# xxxxxx_001_sh2_RTC.net
KiCad netlist of a schematic drawn in Altium Designer
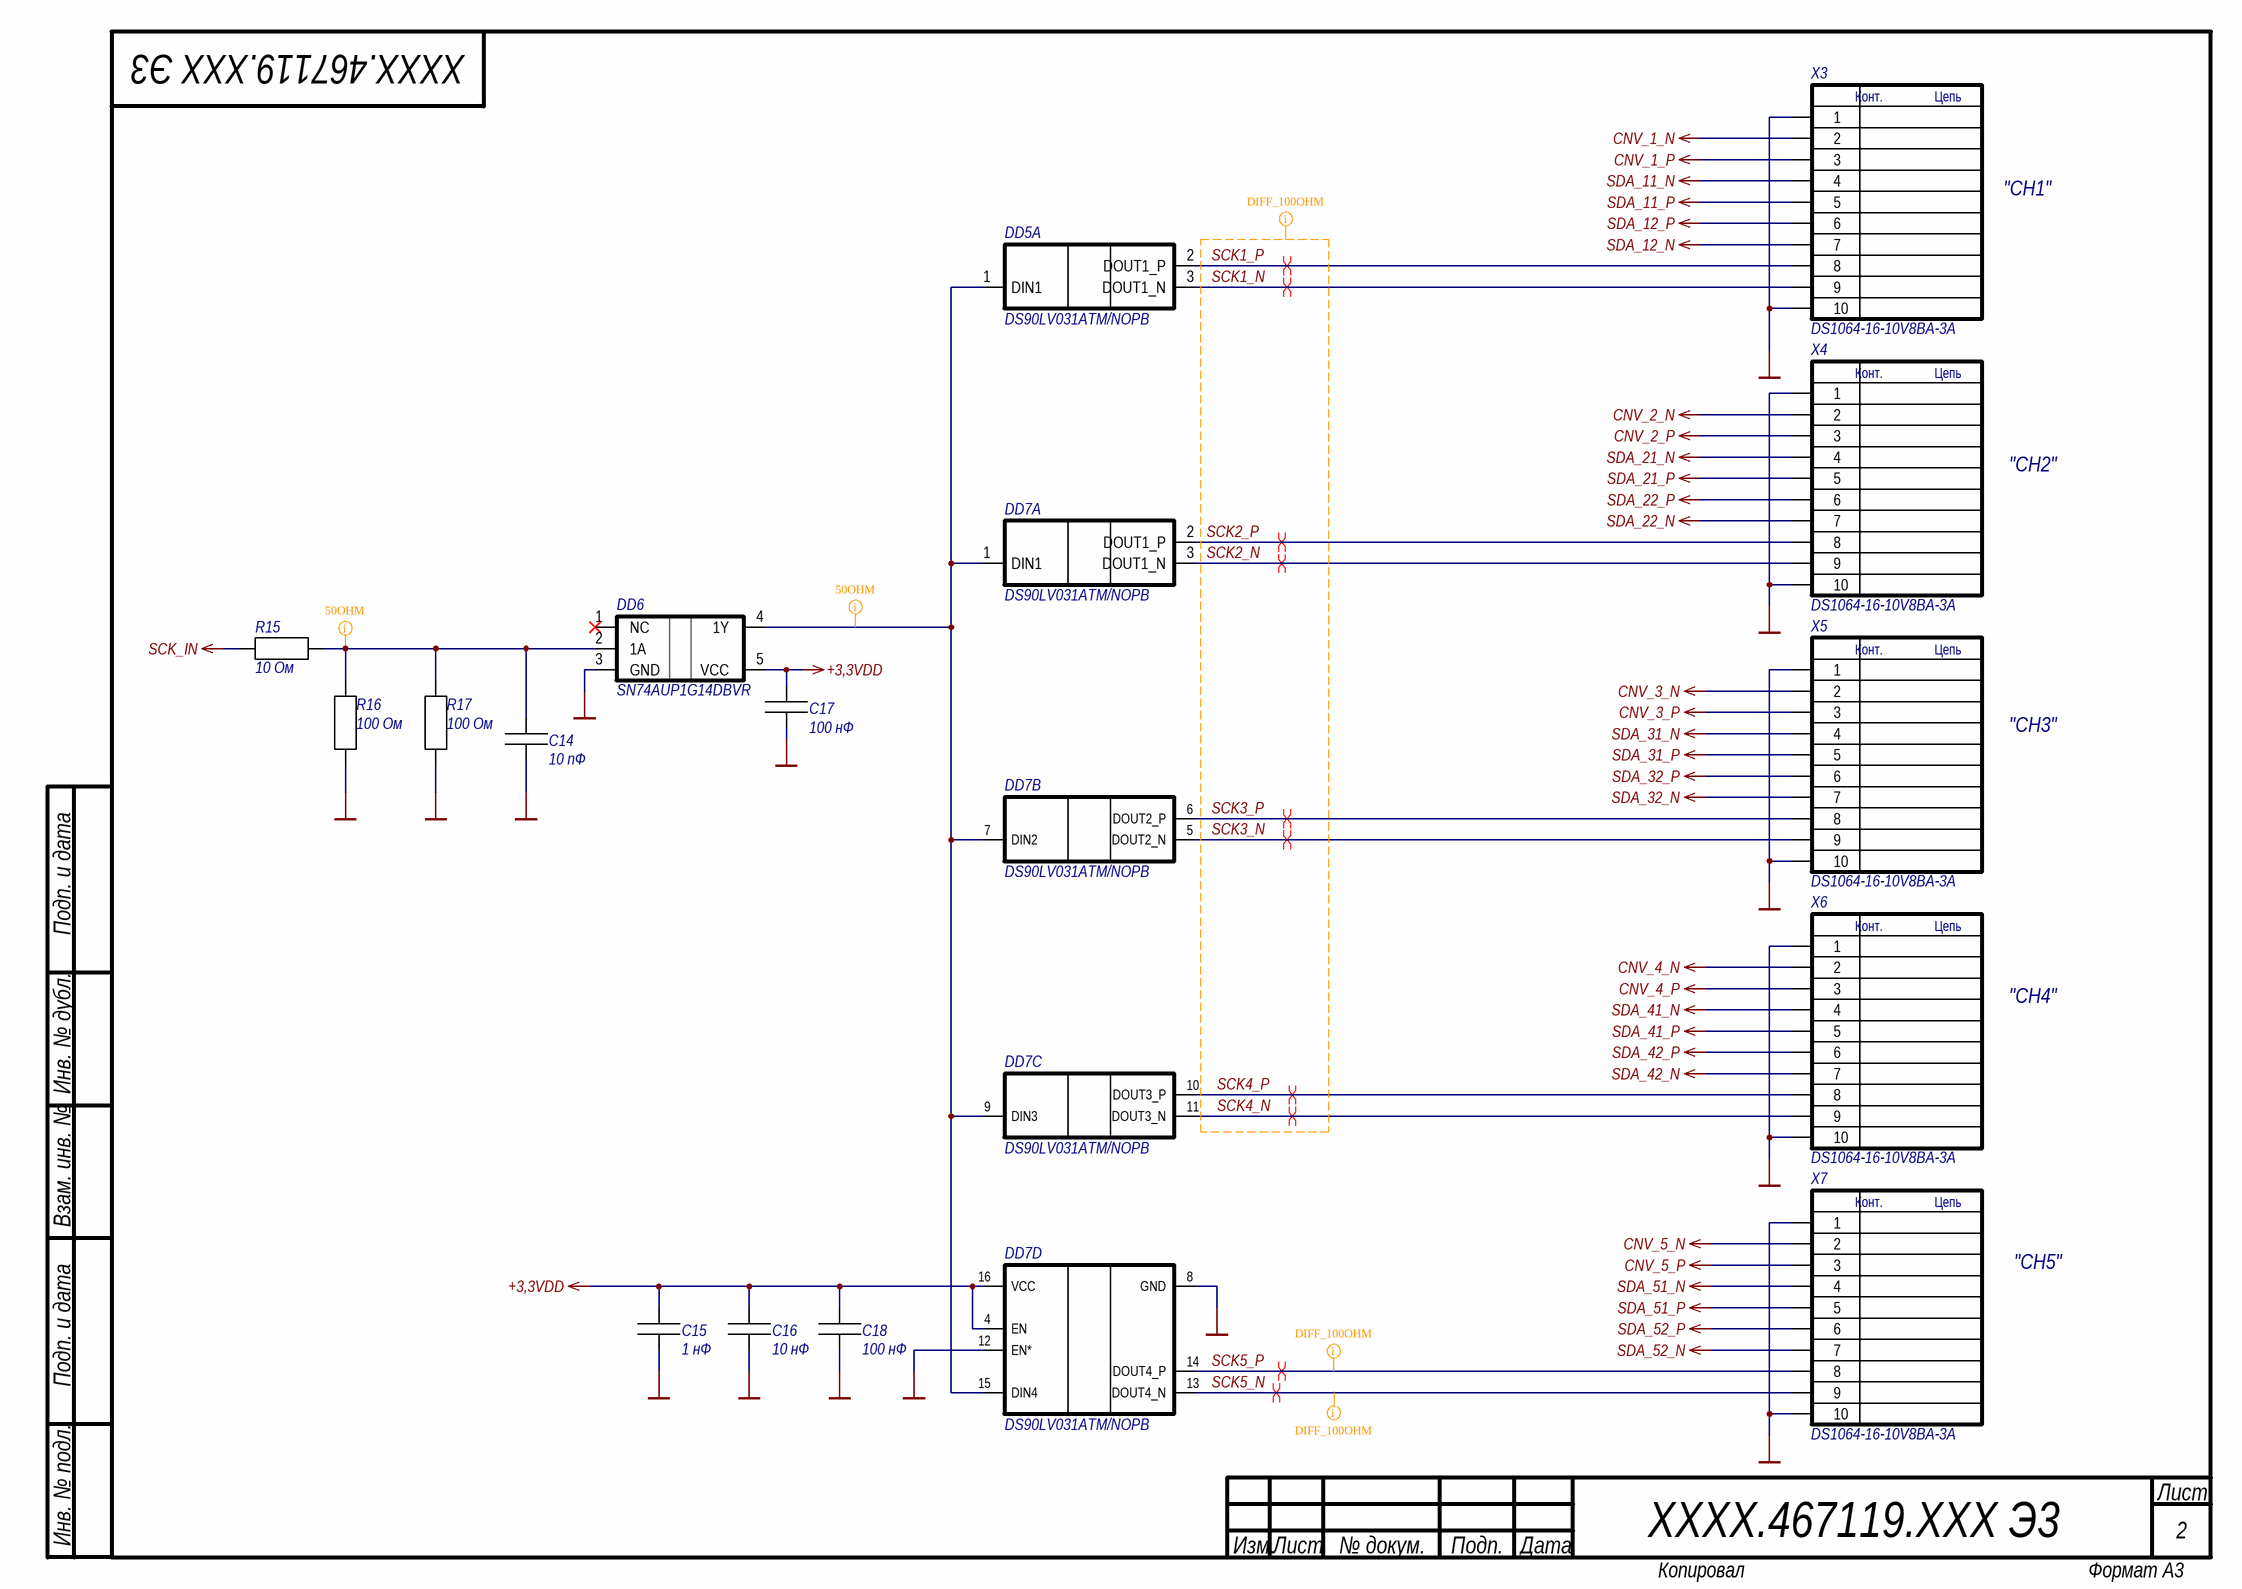
[diagram p0: xxxxxx.001_sh2_RTC.SchDoc]

(export (version "E")
  (design (tool "Eeschema 10.0.6"))
  (components
    (comp (ref "C14")
      (value "10 пФ")
      (footprint "CAPC160X080X080N")
      (description "Multilayer Ceramic Chip Capacitor")
      (fields (field (name "MANUFACTURER") "Yageo") (field (name "VOLTAGE") "50 В"))
      (libsource (lib "xxxxxx001_RTC") (part "CAP_NP"))
    )
    (comp (ref "C15")
      (value "1 нФ")
      (footprint "CAPC160X080X080N")
      (description "Chip Monolithic Ceramic Capacitor")
      (fields (field (name "MANUFACTURER") "Murata") (field (name "VOLTAGE") "50 В"))
      (libsource (lib "xxxxxx001_RTC") (part "CAP_NP"))
    )
    (comp (ref "C16")
      (value "10 нФ")
      (footprint "CAPC160X080X080N")
      (description "Chip Monolithic Ceramic Capacitor")
      (fields (field (name "MANUFACTURER") "Murata") (field (name "VOLTAGE") "25 В"))
      (libsource (lib "xxxxxx001_RTC") (part "CAP_NP"))
    )
    (comp (ref "C17")
      (value "100 нФ")
      (footprint "CAPC160X080X080N")
      (description "Chip Monolithic Ceramic Capacitor")
      (fields (field (name "MANUFACTURER") "Murata") (field (name "VOLTAGE") "25 В"))
      (libsource (lib "xxxxxx001_RTC") (part "CAP_NP"))
    )
    (comp (ref "C18")
      (value "100 нФ")
      (footprint "CAPC160X080X080N")
      (description "Chip Monolithic Ceramic Capacitor")
      (fields (field (name "MANUFACTURER") "Murata") (field (name "VOLTAGE") "25 В"))
      (libsource (lib "xxxxxx001_RTC") (part "CAP_NP"))
    )
    (comp (ref "DD5")
      (value "DS90LV031ATM/NOPB")
      (footprint "SOIC127P600X175-16N")
      (description "3-V LVDS Quad CMOS Differential Line Driver")
      (fields (field (name "MANUFACTURER") "Texas Instruments"))
      (libsource (lib "xxxxxx001_RTC") (part "DS90LV031ATM"))
    )
    (comp (ref "DD6")
      (value "SN74AUP1G14DBVR")
      (footprint "TI_DBV0005A_SOT23_5")
      (description "Low-Power Single Schmitt-Trigger Inverter")
      (fields (field (name "MANUFACTURER") "Texas Instruments"))
      (libsource (lib "xxxxxx001_RTC") (part "SN74AUP1G14"))
    )
    (comp (ref "DD7")
      (value "DS90LV031ATM/NOPB")
      (footprint "SOIC127P600X175-16N")
      (description "3-V LVDS Quad CMOS Differential Line Driver")
      (fields (field (name "MANUFACTURER") "Texas Instruments"))
      (libsource (lib "xxxxxx001_RTC") (part "DS90LV031ATM"))
    )
    (comp (ref "R15")
      (value "10 Ом")
      (footprint "RESC160X080X045N")
      (description "General Purpose Chip Resistor")
      (fields (field (name "MANUFACTURER") "Yageo") (field (name "POWER") "100 мВт"))
      (libsource (lib "") (part "RES_1"))
    )
    (comp (ref "R16")
      (value "100 Ом")
      (footprint "RESC160X080X045N")
      (description "General Purpose Chip Resistor")
      (fields (field (name "MANUFACTURER") "Yageo") (field (name "POWER") "100 мВт"))
      (libsource (lib "xxxxxx001_RTC") (part "RES"))
    )
    (comp (ref "R17")
      (value "100 Ом")
      (footprint "RESC160X080X045N")
      (description "General Purpose Chip Resistor")
      (fields (field (name "MANUFACTURER") "Yageo") (field (name "POWER") "100 мВт"))
      (libsource (lib "xxxxxx001_RTC") (part "RES"))
    )
    (comp (ref "X3")
      (value "DS1064-16-10V8BA-3A")
      (footprint "BHTH127x254_2X5")
      (description "1.27mm Box Header V/T Type H=7.1mm, 10 pin")
      (fields (field (name "MANUFACTURER") "Connfly"))
      (libsource (lib "xxxxxx001_RTC") (part "CONN_10P"))
    )
    (comp (ref "X4")
      (value "DS1064-16-10V8BA-3A")
      (footprint "BHTH127x254_2X5")
      (description "1.27mm Box Header V/T Type H=7.1mm, 10 pin")
      (fields (field (name "MANUFACTURER") "Connfly"))
      (libsource (lib "xxxxxx001_RTC") (part "CONN_10P"))
    )
    (comp (ref "X5")
      (value "DS1064-16-10V8BA-3A")
      (footprint "BHTH127x254_2X5")
      (description "1.27mm Box Header V/T Type H=7.1mm, 10 pin")
      (fields (field (name "MANUFACTURER") "Connfly"))
      (libsource (lib "xxxxxx001_RTC") (part "CONN_10P"))
    )
    (comp (ref "X6")
      (value "DS1064-16-10V8BA-3A")
      (footprint "BHTH127x254_2X5")
      (description "1.27mm Box Header V/T Type H=7.1mm, 10 pin")
      (fields (field (name "MANUFACTURER") "Connfly"))
      (libsource (lib "xxxxxx001_RTC") (part "CONN_10P"))
    )
    (comp (ref "X7")
      (value "DS1064-16-10V8BA-3A")
      (footprint "BHTH127x254_2X5")
      (description "1.27mm Box Header V/T Type H=7.1mm, 10 pin")
      (fields (field (name "MANUFACTURER") "Connfly"))
      (libsource (lib "xxxxxx001_RTC") (part "CONN_10P"))
    )
  )
  (nets
    (net (code "1") (name "+3,3VDD") (class "Default")
      (node (ref "C15") (pin "1") (pinfunction "1_1") (pintype "passive"))
      (node (ref "C16") (pin "1") (pinfunction "1_1") (pintype "passive"))
      (node (ref "C17") (pin "1") (pinfunction "1_1") (pintype "passive"))
      (node (ref "C18") (pin "1") (pinfunction "1_1") (pintype "passive"))
      (node (ref "DD6") (pin "5") (pinfunction "VCC_5") (pintype "passive"))
      (node (ref "DD7") (pin "16") (pinfunction "VCC_16") (pintype "passive"))
      (node (ref "DD7") (pin "4") (pinfunction "EN_4") (pintype "passive"))
    )
    (net (code "2") (name "/SCK1_N") (class "Default")
      (node (ref "DD5") (pin "3") (pinfunction "DOUT1_N_3") (pintype "passive"))
      (node (ref "X3") (pin "9") (pinfunction "9_9") (pintype "passive"))
    )
    (net (code "3") (name "/SCK1_P") (class "Default")
      (node (ref "DD5") (pin "2") (pinfunction "DOUT1_P_2") (pintype "passive"))
      (node (ref "X3") (pin "8") (pinfunction "8_8") (pintype "passive"))
    )
    (net (code "4") (name "/SCK2_N") (class "Default")
      (node (ref "DD7") (pin "3") (pinfunction "DOUT1_N_3") (pintype "passive"))
      (node (ref "X4") (pin "9") (pinfunction "9_9") (pintype "passive"))
    )
    (net (code "5") (name "/SCK2_P") (class "Default")
      (node (ref "DD7") (pin "2") (pinfunction "DOUT1_P_2") (pintype "passive"))
      (node (ref "X4") (pin "8") (pinfunction "8_8") (pintype "passive"))
    )
    (net (code "6") (name "/SCK3_N") (class "Default")
      (node (ref "DD7") (pin "5") (pinfunction "DOUT2_N_5") (pintype "passive"))
      (node (ref "X5") (pin "9") (pinfunction "9_9") (pintype "passive"))
    )
    (net (code "7") (name "/SCK3_P") (class "Default")
      (node (ref "DD7") (pin "6") (pinfunction "DOUT2_P_6") (pintype "passive"))
      (node (ref "X5") (pin "8") (pinfunction "8_8") (pintype "passive"))
    )
    (net (code "8") (name "/SCK4_N") (class "Default")
      (node (ref "DD7") (pin "11") (pinfunction "DOUT3_N_11") (pintype "passive"))
      (node (ref "X6") (pin "9") (pinfunction "9_9") (pintype "passive"))
    )
    (net (code "9") (name "/SCK4_P") (class "Default")
      (node (ref "DD7") (pin "10") (pinfunction "DOUT3_P_10") (pintype "passive"))
      (node (ref "X6") (pin "8") (pinfunction "8_8") (pintype "passive"))
    )
    (net (code "10") (name "/SCK5_N") (class "Default")
      (node (ref "DD7") (pin "13") (pinfunction "DOUT4_N_13") (pintype "passive"))
      (node (ref "X7") (pin "9") (pinfunction "9_9") (pintype "passive"))
    )
    (net (code "11") (name "/SCK5_P") (class "Default")
      (node (ref "DD7") (pin "14") (pinfunction "DOUT4_P_14") (pintype "passive"))
      (node (ref "X7") (pin "8") (pinfunction "8_8") (pintype "passive"))
    )
    (net (code "12") (name "CNV_1_N") (class "Default")
      (node (ref "X3") (pin "2") (pinfunction "2_2") (pintype "passive"))
    )
    (net (code "13") (name "CNV_1_P") (class "Default")
      (node (ref "X3") (pin "3") (pinfunction "3_3") (pintype "passive"))
    )
    (net (code "14") (name "CNV_2_N") (class "Default")
      (node (ref "X4") (pin "2") (pinfunction "2_2") (pintype "passive"))
    )
    (net (code "15") (name "CNV_2_P") (class "Default")
      (node (ref "X4") (pin "3") (pinfunction "3_3") (pintype "passive"))
    )
    (net (code "16") (name "CNV_3_N") (class "Default")
      (node (ref "X5") (pin "2") (pinfunction "2_2") (pintype "passive"))
    )
    (net (code "17") (name "CNV_3_P") (class "Default")
      (node (ref "X5") (pin "3") (pinfunction "3_3") (pintype "passive"))
    )
    (net (code "18") (name "CNV_4_N") (class "Default")
      (node (ref "X6") (pin "2") (pinfunction "2_2") (pintype "passive"))
    )
    (net (code "19") (name "CNV_4_P") (class "Default")
      (node (ref "X6") (pin "3") (pinfunction "3_3") (pintype "passive"))
    )
    (net (code "20") (name "CNV_5_N") (class "Default")
      (node (ref "X7") (pin "2") (pinfunction "2_2") (pintype "passive"))
    )
    (net (code "21") (name "CNV_5_P") (class "Default")
      (node (ref "X7") (pin "3") (pinfunction "3_3") (pintype "passive"))
    )
    (net (code "22") (name "GND") (class "Default")
      (node (ref "C14") (pin "2") (pinfunction "2_2") (pintype "passive"))
      (node (ref "C15") (pin "2") (pinfunction "2_2") (pintype "passive"))
      (node (ref "C16") (pin "2") (pinfunction "2_2") (pintype "passive"))
      (node (ref "C17") (pin "2") (pinfunction "2_2") (pintype "passive"))
      (node (ref "C18") (pin "2") (pinfunction "2_2") (pintype "passive"))
      (node (ref "DD6") (pin "3") (pinfunction "GND_3") (pintype "passive"))
      (node (ref "DD7") (pin "12") (pinfunction "EN*_12") (pintype "passive"))
      (node (ref "DD7") (pin "8") (pinfunction "GND_8") (pintype "passive"))
      (node (ref "R16") (pin "2") (pinfunction "2_2") (pintype "passive"))
      (node (ref "R17") (pin "2") (pinfunction "2_2") (pintype "passive"))
      (node (ref "X3") (pin "1") (pinfunction "1_1") (pintype "passive"))
      (node (ref "X3") (pin "10") (pinfunction "10_10") (pintype "passive"))
      (node (ref "X4") (pin "1") (pinfunction "1_1") (pintype "passive"))
      (node (ref "X4") (pin "10") (pinfunction "10_10") (pintype "passive"))
      (node (ref "X5") (pin "1") (pinfunction "1_1") (pintype "passive"))
      (node (ref "X5") (pin "10") (pinfunction "10_10") (pintype "passive"))
      (node (ref "X6") (pin "1") (pinfunction "1_1") (pintype "passive"))
      (node (ref "X6") (pin "10") (pinfunction "10_10") (pintype "passive"))
      (node (ref "X7") (pin "1") (pinfunction "1_1") (pintype "passive"))
      (node (ref "X7") (pin "10") (pinfunction "10_10") (pintype "passive"))
    )
    (net (code "23") (name "Net-(DD5A-DIN1)") (class "Default")
      (node (ref "DD5") (pin "1") (pinfunction "DIN1_1") (pintype "passive"))
      (node (ref "DD6") (pin "4") (pinfunction "1Y_4") (pintype "passive"))
      (node (ref "DD7") (pin "1") (pinfunction "DIN1_1") (pintype "passive"))
      (node (ref "DD7") (pin "15") (pinfunction "DIN4_15") (pintype "passive"))
      (node (ref "DD7") (pin "7") (pinfunction "DIN2_7") (pintype "passive"))
      (node (ref "DD7") (pin "9") (pinfunction "DIN3_9") (pintype "passive"))
    )
    (net (code "24") (name "Net-(DD6-1A)") (class "Default")
      (node (ref "C14") (pin "1") (pinfunction "1_1") (pintype "passive"))
      (node (ref "DD6") (pin "2") (pinfunction "1A_2") (pintype "passive"))
      (node (ref "R15") (pin "2") (pinfunction "2_2") (pintype "passive"))
      (node (ref "R16") (pin "1") (pinfunction "1_1") (pintype "passive"))
      (node (ref "R17") (pin "1") (pinfunction "1_1") (pintype "passive"))
    )
    (net (code "25") (name "SCK_IN") (class "Default")
      (node (ref "R15") (pin "1") (pinfunction "1_1") (pintype "passive"))
    )
    (net (code "26") (name "SDA_11_N") (class "Default")
      (node (ref "X3") (pin "4") (pinfunction "4_4") (pintype "passive"))
    )
    (net (code "27") (name "SDA_11_P") (class "Default")
      (node (ref "X3") (pin "5") (pinfunction "5_5") (pintype "passive"))
    )
    (net (code "28") (name "SDA_12_N") (class "Default")
      (node (ref "X3") (pin "7") (pinfunction "7_7") (pintype "passive"))
    )
    (net (code "29") (name "SDA_12_P") (class "Default")
      (node (ref "X3") (pin "6") (pinfunction "6_6") (pintype "passive"))
    )
    (net (code "30") (name "SDA_21_N") (class "Default")
      (node (ref "X4") (pin "4") (pinfunction "4_4") (pintype "passive"))
    )
    (net (code "31") (name "SDA_21_P") (class "Default")
      (node (ref "X4") (pin "5") (pinfunction "5_5") (pintype "passive"))
    )
    (net (code "32") (name "SDA_22_N") (class "Default")
      (node (ref "X4") (pin "7") (pinfunction "7_7") (pintype "passive"))
    )
    (net (code "33") (name "SDA_22_P") (class "Default")
      (node (ref "X4") (pin "6") (pinfunction "6_6") (pintype "passive"))
    )
    (net (code "34") (name "SDA_31_N") (class "Default")
      (node (ref "X5") (pin "4") (pinfunction "4_4") (pintype "passive"))
    )
    (net (code "35") (name "SDA_31_P") (class "Default")
      (node (ref "X5") (pin "5") (pinfunction "5_5") (pintype "passive"))
    )
    (net (code "36") (name "SDA_32_N") (class "Default")
      (node (ref "X5") (pin "7") (pinfunction "7_7") (pintype "passive"))
    )
    (net (code "37") (name "SDA_32_P") (class "Default")
      (node (ref "X5") (pin "6") (pinfunction "6_6") (pintype "passive"))
    )
    (net (code "38") (name "SDA_41_N") (class "Default")
      (node (ref "X6") (pin "4") (pinfunction "4_4") (pintype "passive"))
    )
    (net (code "39") (name "SDA_41_P") (class "Default")
      (node (ref "X6") (pin "5") (pinfunction "5_5") (pintype "passive"))
    )
    (net (code "40") (name "SDA_42_N") (class "Default")
      (node (ref "X6") (pin "7") (pinfunction "7_7") (pintype "passive"))
    )
    (net (code "41") (name "SDA_42_P") (class "Default")
      (node (ref "X6") (pin "6") (pinfunction "6_6") (pintype "passive"))
    )
    (net (code "42") (name "SDA_51_N") (class "Default")
      (node (ref "X7") (pin "4") (pinfunction "4_4") (pintype "passive"))
    )
    (net (code "43") (name "SDA_51_P") (class "Default")
      (node (ref "X7") (pin "5") (pinfunction "5_5") (pintype "passive"))
    )
    (net (code "44") (name "SDA_52_N") (class "Default")
      (node (ref "X7") (pin "7") (pinfunction "7_7") (pintype "passive"))
    )
    (net (code "45") (name "SDA_52_P") (class "Default")
      (node (ref "X7") (pin "6") (pinfunction "6_6") (pintype "passive"))
    )
    (net (code "46") (name "unconnected-(DD6-NC-Pad1)") (class "Default")
      (node (ref "DD6") (pin "1") (pinfunction "NC_1") (pintype "passive+no_connect"))
    )
  )
)
